# 105358-3SC001-01-A_IO_BRD.net
KiCad netlist of a schematic drawn in Altium Designer
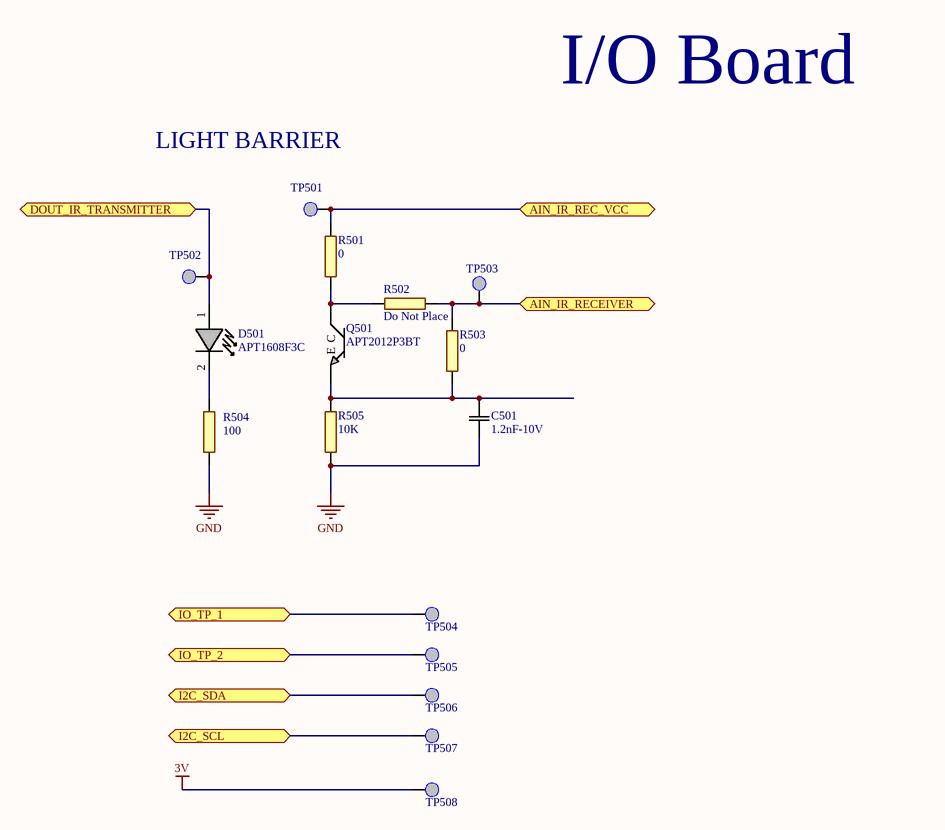
[diagram p0: 105358-3SC001-01-A_IO_BRD.SchDoc]

(export (version "E")
  (design (tool "Eeschema 10.0.6"))
  (components
    (comp (ref "C501")
      (value "1.2nF-10V")
      (footprint "0402C_HIGH_DENSITY")
      (description "1.2nF ±10% 10V U2J Ceramic Capacitor 0402")
      (fields
        (field (name "MANUFACTURER PART NUMBER") "GRM1557U1A122JA01D")
        (field (name "MANUFACTURER") "Murata Electronics North America")
      )
      (libsource (lib "ConnectMedical") (part "0402C-1.2nF-10V"))
    )
    (comp (ref "D501")
      (value "APT1608F3C")
      (footprint "APT1608F3C")
      (description "0603 INFRARED DIODE")
      (fields
        (field (name "MANUFACTURER") "Kingbright")
        (field (name "DIGI-KEY PART NUMBER") "754-1433-1-ND")
      )
      (libsource (lib "ConnectMedical") (part "APT1608F3C"))
    )
    (comp (ref "Q501")
      (value "APT2012P3BT")
      (footprint "APT2012P3BT")
      (description "0805 PHOTOTRANSISTOR")
      (fields
        (field (name "MANUFACTURER") "Kingbright")
        (field (name "DIGI-KEY PART NUMBER") "754-1436-1-ND")
      )
      (libsource (lib "ConnectMedical") (part "APT2012P3BT"))
    )
    (comp (ref "R501")
      (value "0")
      (footprint "0402R-GENERIC")
      (description "RES SMD 0.0OHM JUMPER 1/16W 0402")
      (fields (field (name "DIGI-KEY PART NUMBER") "311-0.0JRCT-ND") (field (name "MANUFACTURER") "Yageo"))
      (libsource (lib "ConnectMedical") (part "0402R-0 OHM-0.063W"))
    )
    (comp (ref "R502")
      (value "Do Not Place")
      (footprint "0402R-GENERIC")
      (libsource (lib "ConnectMedical") (part "0402R-Do Not Place"))
    )
    (comp (ref "R503")
      (value "0")
      (footprint "0402R-GENERIC")
      (description "RES SMD 0.0OHM JUMPER 1/16W 0402")
      (fields (field (name "DIGI-KEY PART NUMBER") "311-0.0JRCT-ND") (field (name "MANUFACTURER") "Yageo"))
      (libsource (lib "ConnectMedical") (part "0402R-0 OHM-0.063W"))
    )
    (comp (ref "R504")
      (value "100")
      (footprint "0402R-GENERIC")
      (description "RES SMD 100OHM 1% 1/16W 0402")
      (fields (field (name "DIGI-KEY PART NUMBER") "311-100LRCT-ND") (field (name "MANUFACTURER") "Yageo"))
      (libsource (lib "ConnectMedical") (part "0402R-100 OHM-1%-0.063W"))
    )
    (comp (ref "R505")
      (value "10K")
      (footprint "0402R-GENERIC")
      (description "RES SMD 10kOHM 1% 1/16W 0402")
      (fields (field (name "DIGI-KEY PART NUMBER") "311-10.0KLRCT-ND") (field (name "MANUFACTURER") "Yageo"))
      (libsource (lib "ConnectMedical") (part "0402R-10k OHM-1%-0.063W"))
    )
    (comp (ref "TP501")
      (value "TEST POINT")
      (footprint "PAD TEST POINT")
      (description "Testing Poiny")
      (libsource (lib "ConnectMedical") (part "TEST POINT"))
    )
    (comp (ref "TP502")
      (value "TEST POINT")
      (footprint "PAD TEST POINT")
      (description "Testing Poiny")
      (libsource (lib "ConnectMedical") (part "TEST POINT"))
    )
    (comp (ref "TP503")
      (value "TEST POINT")
      (footprint "PAD TEST POINT")
      (description "Testing Poiny")
      (libsource (lib "ConnectMedical") (part "TEST POINT"))
    )
    (comp (ref "TP504")
      (value "TEST POINT")
      (footprint "PAD TEST POINT")
      (description "Testing Poiny")
      (libsource (lib "ConnectMedical") (part "TEST POINT"))
    )
    (comp (ref "TP505")
      (value "TEST POINT")
      (footprint "PAD TEST POINT")
      (description "Testing Poiny")
      (libsource (lib "ConnectMedical") (part "TEST POINT"))
    )
    (comp (ref "TP506")
      (value "TEST POINT")
      (footprint "PAD TEST POINT")
      (description "Testing Poiny")
      (libsource (lib "ConnectMedical") (part "TEST POINT"))
    )
    (comp (ref "TP507")
      (value "TEST POINT")
      (footprint "PAD TEST POINT")
      (description "Testing Poiny")
      (libsource (lib "ConnectMedical") (part "TEST POINT"))
    )
    (comp (ref "TP508")
      (value "TEST POINT")
      (footprint "PAD TEST POINT")
      (description "Testing Poiny")
      (libsource (lib "ConnectMedical") (part "TEST POINT"))
    )
  )
  (nets
    (net (code "1") (name "/AIN_IR_RECEIVER") (class "Default")
      (node (ref "R502") (pin "2") (pintype "passive"))
      (node (ref "R503") (pin "1") (pintype "passive"))
      (node (ref "TP503") (pin "1") (pinfunction "Test_Point_1") (pintype "passive"))
    )
    (net (code "2") (name "/AIN_IR_REC_VCC") (class "Default")
      (node (ref "R501") (pin "1") (pintype "passive"))
      (node (ref "TP501") (pin "1") (pinfunction "Test_Point_1") (pintype "passive"))
    )
    (net (code "3") (name "/DOUT_IR_TRANSMITTER") (class "Default")
      (node (ref "D501") (pin "1") (pinfunction "A_1") (pintype "passive"))
      (node (ref "TP502") (pin "1") (pinfunction "Test_Point_1") (pintype "passive"))
    )
    (net (code "4") (name "/I2C_SCL") (class "Default")
      (node (ref "TP507") (pin "1") (pinfunction "Test_Point_1") (pintype "passive"))
    )
    (net (code "5") (name "/I2C_SDA") (class "Default")
      (node (ref "TP506") (pin "1") (pinfunction "Test_Point_1") (pintype "passive"))
    )
    (net (code "6") (name "/IO_TP_1") (class "Default")
      (node (ref "TP504") (pin "1") (pinfunction "Test_Point_1") (pintype "passive"))
    )
    (net (code "7") (name "/IO_TP_2") (class "Default")
      (node (ref "TP505") (pin "1") (pinfunction "Test_Point_1") (pintype "passive"))
    )
    (net (code "8") (name "3V") (class "Default")
      (node (ref "TP508") (pin "1") (pinfunction "Test_Point_1") (pintype "passive"))
    )
    (net (code "9") (name "GND") (class "Default")
      (node (ref "C501") (pin "1") (pinfunction "1_1") (pintype "passive"))
      (node (ref "R504") (pin "2") (pintype "passive"))
      (node (ref "R505") (pin "2") (pintype "passive"))
    )
    (net (code "10") (name "Net-(D501-K)") (class "Default")
      (node (ref "D501") (pin "2") (pinfunction "K_2") (pintype "passive"))
      (node (ref "R504") (pin "1") (pintype "passive"))
    )
    (net (code "11") (name "Net-(Q501-C)") (class "Default")
      (node (ref "Q501") (pin "2") (pinfunction "C_2") (pintype "passive"))
      (node (ref "R501") (pin "2") (pintype "passive"))
      (node (ref "R502") (pin "1") (pintype "passive"))
    )
    (net (code "12") (name "Net-(Q501-E)") (class "Default")
      (node (ref "C501") (pin "2") (pinfunction "2_2") (pintype "passive"))
      (node (ref "Q501") (pin "1") (pinfunction "E_1") (pintype "passive"))
      (node (ref "R503") (pin "2") (pintype "passive"))
      (node (ref "R505") (pin "1") (pintype "passive"))
    )
  )
)
